# Eval_Board.net
KiCad netlist of a schematic drawn in Altium Designer
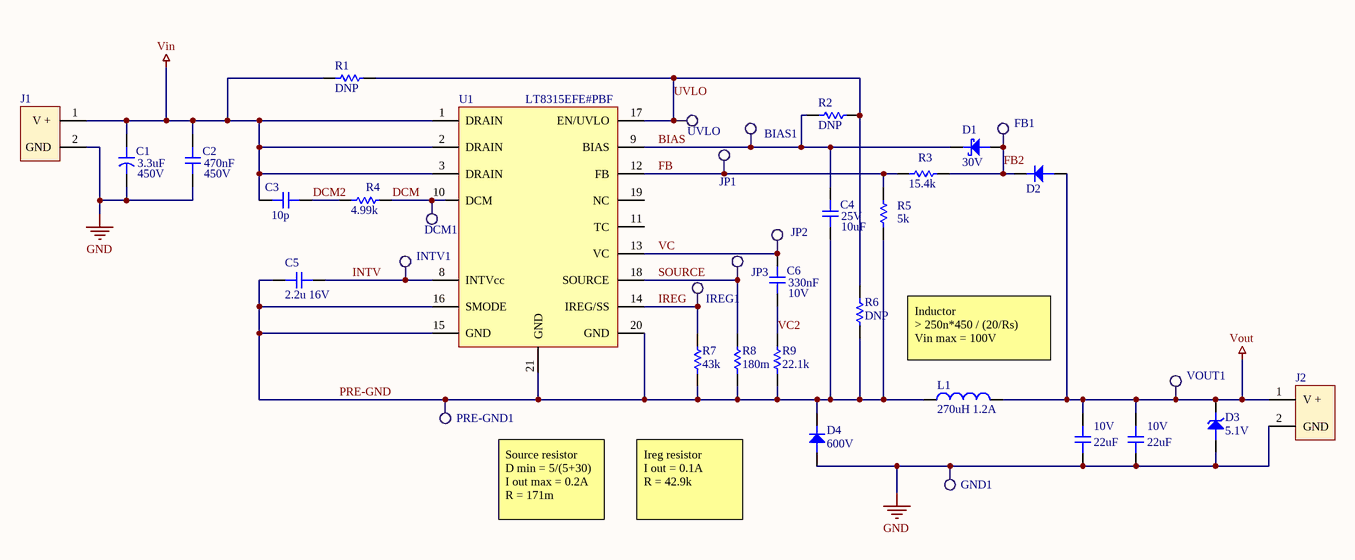
[diagram p0: Eval_Board.SchDoc]

(export (version "E")
  (design (tool "Eeschema 10.0.6"))
  (components
    (comp (ref "BIAS1")
      (value "Testpoint2")
      (footprint "TP2")
      (description "Single layer pad TP")
      (libsource (lib "Misc") (part "Testpoint2"))
    )
    (comp (ref "C1")
      (value "3.3uF 450V")
      (footprint "CAPAE125136X145M")
      (description "Al Cap UJ series SMT 3.3uF 450V")
      (fields
        (field (name "MANUFACTURER") "Nichicon")
        (field (name "MANUFACTURER PART NUMBER") "UUJ2W3R3MNQ1MS")
        (field (name "CAPACITANCE") "3.3uF")
        (field (name "VOLTAGE RATING (DC)") "450V")
      )
      (libsource (lib "DC_converter_sch") (part "UUJ2W3R3MNQ1MS"))
    )
    (comp (ref "C2")
      (value "0.47uF 450V 1812")
      (footprint "CAPC4532X28N")
      (description "Automotive Grade MLCC, 1812, X7T, 450V, 0.47 F, 20%, 2.30mm")
      (fields
        (field (name "MANUFACTURER") "TDK")
        (field (name "MANUFACTURER PART NUMBER") "CGA8N4X7T2W474M230KA")
        (field (name "CAPACITANCE") "470nF")
        (field (name "VOLTAGE RATING") "450V")
      )
      (libsource (lib "DC_converter_sch") (part "CGA8N4X7T2W474M230KA"))
    )
    (comp (ref "C3")
      (value "10p")
      (footprint "CAP-0805")
      (description "CAP CER 0805 10PF 25V")
      (fields
        (field (name "MANUFACTURER") "Murata")
        (field (name "MANUFACTURER PART NUMBER") "GCQ1555C1H9R6DB01D")
      )
      (libsource (lib "DC_converter_sch") (part "GCQ1555C1H9R6DB01D"))
    )
    (comp (ref "C4")
      (value "GRM21BR61E106MA73L")
      (footprint "CAP-0805")
      (description "Capacitor, 10 µF, 25 V, 0805 [2012 Metric], ± 20%, X5R, GRM Series")
      (fields
        (field (name "MANUFACTURER") "Murata")
        (field (name "TOLERANCE") "20%")
        (field (name "VOLTAGE RATING") "25V")
        (field (name "CAPACITANCE") "10uF")
      )
      (libsource (lib "DC_converter_sch") (part "GRM21BR61E106MA73L"))
    )
    (comp (ref "C5")
      (value "2.2u 16V")
      (footprint "CAP-0805")
      (description "Cap Ceramic 2.2uF 16V X7R 10% SMD 0805 125C Embossed T/R")
      (fields
        (field (name "MANUFACTURER") "Samsung")
        (field (name "MANUFACTURER PART NUMBER") "CL21B225KOFNFNE")
      )
      (libsource (lib "DC_converter_sch") (part "CL21B225KOFNFNE"))
    )
    (comp (ref "C6")
      (value "0.33u 10V")
      (footprint "CAP-0805")
      (description "CAP CER 0.33UF 10V X7R 0805")
      (fields
        (field (name "MANUFACTURER") "TDK")
        (field (name "MANUFACTURER PART NUMBER") "CGJ4J2X7R1A334K125AA")
        (field (name "VOLTAGE RATING") "10V")
        (field (name "CAPACITANCE") "330nF")
      )
      (libsource (lib "DC_converter_sch") (part "CGJ4J2X7R1A334K125AA"))
    )
    (comp (ref "C7")
      (value "GRM21BR61A226ME51L")
      (footprint "CAP-0805")
      (description "CAP, MLCC, X5R, 22UF, 10V, 0805")
      (fields
        (field (name "MANUFACTURER") "Murata")
        (field (name "TOLERANCE") "20%")
        (field (name "VOLTAGE RATING") "10V")
        (field (name "CAPACITANCE") "22uF")
      )
      (libsource (lib "DC_converter_sch") (part "GRM21BR61A226ME51L"))
    )
    (comp (ref "C8")
      (value "GRM21BR61A226ME51L")
      (footprint "CAP-0805")
      (description "CAP, MLCC, X5R, 22UF, 10V, 0805")
      (fields
        (field (name "MANUFACTURER") "Murata")
        (field (name "TOLERANCE") "20%")
        (field (name "VOLTAGE RATING") "10V")
        (field (name "CAPACITANCE") "22uF")
      )
      (libsource (lib "DC_converter_sch") (part "GRM21BR61A226ME51L"))
    )
    (comp (ref "D1")
      (value "30V")
      (footprint "PMEG3010EGWX")
      (fields
        (field (name "MANUFACTURER") "Nexperia")
        (field (name "MANUFACTURER PART NUMBER") "PMEG3010EGWX")
      )
      (libsource (lib "DC_converter_sch") (part "PMEG3010EGWX"))
    )
    (comp (ref "D2")
      (value "CMMR1U-06TRPBFREE")
      (footprint "SODFL375X108-2N")
      (fields (field (name "MANUFACTURER") "Central Semiconductor"))
      (libsource (lib "DC_converter_sch") (part "CMMR1U-06TRPBFREE"))
    )
    (comp (ref "D3")
      (value "5.1V")
      (footprint "SOT95P230X110-3N")
      (description "Zener Diode Single 5.1V 5% 60Ohm 250mW Automotive 3-Pin SOT-23 T/R")
      (fields
        (field (name "MANUFACTURER") "Nexperia")
        (field (name "MANUFACTURER PART NUMBER") "BZX84-C5V1,215")
      )
      (libsource (lib "DC_converter_sch") (part "BZX84-C5V1,215"))
    )
    (comp (ref "D4")
      (value "600V")
      (footprint "D3")
      (fields
        (field (name "MANUFACTURER") "Taiwan Semiconductor")
        (field (name "MANUFACTURER PART NUMBER") "HS2JFSM3G")
      )
      (libsource (lib "DC_converter_sch") (part "HS2JFSM3G"))
    )
    (comp (ref "DCM1")
      (value "Testpoint2")
      (footprint "TP2")
      (description "Single layer pad TP")
      (libsource (lib "Misc") (part "Testpoint2"))
    )
    (comp (ref "FB1")
      (value "Testpoint2")
      (footprint "TP2")
      (description "Single layer pad TP")
      (libsource (lib "Misc") (part "Testpoint2"))
    )
    (comp (ref "GND1")
      (value "Testpoint2")
      (footprint "TP2")
      (description "Single layer pad TP")
      (libsource (lib "Misc") (part "Testpoint2"))
    )
    (comp (ref "INTV1")
      (value "Testpoint2")
      (footprint "TP2")
      (description "Single layer pad TP")
      (libsource (lib "Misc") (part "Testpoint2"))
    )
    (comp (ref "IREG1")
      (value "Testpoint2")
      (footprint "TP2")
      (description "Single layer pad TP")
      (libsource (lib "Misc") (part "Testpoint2"))
    )
    (comp (ref "J1")
      (value "WM4153-ND")
      (footprint "2PIN")
      (description "CONN HEADER R/A 2POS 2.54MM")
      (fields (field (name "MANUFACTURER") "Molex") (field (name "MANUFACTURER PART NUMBER") "0705530106"))
      (libsource (lib "DC_converter_sch") (part "2PIN"))
    )
    (comp (ref "J2")
      (value "WM4153-ND")
      (footprint "2PIN")
      (description "CONN HEADER R/A 2POS 2.54MM")
      (fields (field (name "MANUFACTURER") "Molex") (field (name "MANUFACTURER PART NUMBER") "0705530106"))
      (libsource (lib "") (part "2PIN_1"))
    )
    (comp (ref "JP1")
      (value "Testpoint2")
      (footprint "TP2")
      (description "Single layer pad TP")
      (libsource (lib "Misc") (part "Testpoint2"))
    )
    (comp (ref "JP2")
      (value "Testpoint2")
      (footprint "TP2")
      (description "Single layer pad TP")
      (libsource (lib "Misc") (part "Testpoint2"))
    )
    (comp (ref "JP3")
      (value "Testpoint2")
      (footprint "TP2")
      (description "Single layer pad TP")
      (libsource (lib "Misc") (part "Testpoint2"))
    )
    (comp (ref "L1")
      (value "270uH 1.2A")
      (footprint "PCBComponent_1")
      (description "FIXED IND 270UH 1.2A 410 MOHM")
      (fields
        (field (name "MANUFACTURER") "Bourns")
        (field (name "MANUFACTURER PART NUMBER") "SDR1307-271KL")
      )
      (libsource (lib "DC_converter_sch") (part "SDR1307-271KL"))
    )
    (comp (ref "PRE-GND1")
      (value "Testpoint2")
      (footprint "TP2")
      (description "Single layer pad TP")
      (libsource (lib "Misc") (part "Testpoint2"))
    )
    (comp (ref "R1")
      (value "DNP")
      (footprint "RES-0805")
      (description "Res Thick Film 0805 100 Ohm 1% 1/8W ±100ppm/°C Molded SMD Paper T/R")
      (fields
        (field (name "MANUFACTURER") "Vishay Dale")
        (field (name "MANUFACTURER PART NUMBER") "CRCW0805100RFKEA")
      )
      (libsource (lib "DC_converter_sch") (part "CRCW0805100RFKEA"))
    )
    (comp (ref "R2")
      (value "DNP")
      (footprint "RES-0805")
      (description "Fixed Resistor, Metal Glaze/thick Film, 0.125W, 0ohm, Surface Mount, 0805")
      (fields
        (field (name "MANUFACTURER") "Yageo")
        (field (name "MANUFACTURER PART NUMBER") "AC0805JR-070RL")
      )
      (libsource (lib "DC_converter_sch") (part "AC0805JR-070RL"))
    )
    (comp (ref "R3")
      (value "RMCF0805FT15K4")
      (footprint "RES-0805")
      (description "RES 15.4K OHM 1% 1/8W 0805")
      (fields
        (field (name "MANUFACTURER") "Stackpole Electronics")
        (field (name "TOLERANCE") "1%")
        (field (name "RESISTANCE") "15.4k")
      )
      (libsource (lib "DC_converter_sch") (part "RMCF0805FT15K4"))
    )
    (comp (ref "R4")
      (value "RNCP0805FTD4K99")
      (footprint "RES-0805")
      (description "Res Thin Film 0805 4.99K Ohm 1% 0.25W(1/4W) ±100ppm/°C Sulfur Resistant Pad SMD T/R")
      (fields
        (field (name "MANUFACTURER") "Stackpole Electronics")
        (field (name "TOLERANCE") "1%")
        (field (name "RESISTANCE") "4.99k")
      )
      (libsource (lib "DC_converter_sch") (part "RNCP0805FTD4K99"))
    )
    (comp (ref "R5")
      (value "CRCW08055K00JNTA")
      (footprint "RES-0805")
      (description "Res SMD 5K Ohm 5% 1/8W 0805")
      (fields
        (field (name "MANUFACTURER") "Vishay Dale")
        (field (name "TOLERANCE") "5%")
        (field (name "RESISTANCE") "5k")
      )
      (libsource (lib "DC_converter_sch") (part "CRCW08055K00JNTA"))
    )
    (comp (ref "R6")
      (value "DNP")
      (footprint "RES-0805")
      (description "Res Thick Film 0805 1.6K Ohm 5% 1/8W ±100ppm/°C Molded SMD SMD Paper T/R")
      (fields
        (field (name "MANUFACTURER") "Stackpole Electronics")
        (field (name "MANUFACTURER PART NUMBER") "RMCF0805JT1K60")
      )
      (libsource (lib "DC_converter_sch") (part "RMCF0805JT1K60"))
    )
    (comp (ref "R7")
      (value "43k")
      (footprint "RESC2012X05N")
      (description "Res Thick Film 0805 43K Ohm 5% 0.125W(1/8W) ±200ppm/C Molded SMD Automotive Paper T/R")
      (fields
        (field (name "MANUFACTURER") "Vishay Dale")
        (field (name "MANUFACTURER PART NUMBER") "CRCW080543K0JNEA")
      )
      (libsource (lib "DC_converter_sch") (part "CRCW080543K0JNEA"))
    )
    (comp (ref "R8")
      (value "180m")
      (footprint "RES-0805")
      (description "0.18 Ohm 0805 1% 0.25W Rohs Compliant: Yes")
      (fields (field (name "MANUFACTURER") "Ohmite") (field (name "MANUFACTURER PART NUMBER") "KDV08FR180ET"))
      (libsource (lib "DC_converter_sch") (part "KDV08FR180ET"))
    )
    (comp (ref "R9")
      (value "22.1k")
      (footprint "RESC2012X06N")
      (description "Res Thick Film 0805 22.1K Ohm 1% 1/8W 100ppm/C Molded SMD SMD Paper T/R")
      (fields
        (field (name "MANUFACTURER") "Stackpole Electronics")
        (field (name "MANUFACTURER PART NUMBER") "RMCF0805FG22K1")
      )
      (libsource (lib "DC_converter_sch") (part "RMCF0805FG22K1"))
    )
    (comp (ref "U1")
      (value "LT8315EFE#PBF")
      (footprint "TSOP65P650X120-20N")
      (description "IC REG CTRLR FLYBACK 20TSSOP")
      (fields (field (name "MANUFACTURER") "Analog Devices / Linear Technology"))
      (libsource (lib "DC_converter_sch") (part "LT8315EFE#PBF"))
    )
    (comp (ref "UVLO")
      (value "Testpoint2")
      (footprint "TP2")
      (description "Single layer pad TP")
      (libsource (lib "Misc") (part "Testpoint2"))
    )
    (comp (ref "VOUT1")
      (value "Testpoint2")
      (footprint "TP2")
      (description "Single layer pad TP")
      (libsource (lib "Misc") (part "Testpoint2"))
    )
  )
  (nets
    (net (code "1") (name "/BIAS") (class "Default")
      (node (ref "BIAS1") (pin "1") (pinfunction "1_1") (pintype "passive"))
      (node (ref "C4") (pin "2") (pinfunction "2_2") (pintype "passive"))
      (node (ref "D1") (pin "1") (pinfunction "1_1") (pintype "passive"))
      (node (ref "R2") (pin "1") (pinfunction "1_1") (pintype "passive"))
      (node (ref "U1") (pin "9") (pinfunction "BIAS_9") (pintype "passive"))
    )
    (net (code "2") (name "/DCM") (class "Default")
      (node (ref "DCM1") (pin "1") (pinfunction "1_1") (pintype "passive"))
      (node (ref "R4") (pin "2") (pinfunction "2_2") (pintype "passive"))
      (node (ref "U1") (pin "10") (pinfunction "DCM_10") (pintype "passive"))
    )
    (net (code "3") (name "/DCM2") (class "Default")
      (node (ref "C3") (pin "2") (pinfunction "2_2") (pintype "passive"))
      (node (ref "R4") (pin "1") (pinfunction "1_1") (pintype "passive"))
    )
    (net (code "4") (name "/FB") (class "Default")
      (node (ref "JP1") (pin "1") (pinfunction "1_1") (pintype "passive"))
      (node (ref "R3") (pin "1") (pinfunction "1_1") (pintype "passive"))
      (node (ref "R5") (pin "2") (pinfunction "2_2") (pintype "passive"))
      (node (ref "U1") (pin "12") (pinfunction "FB_12") (pintype "passive"))
    )
    (net (code "5") (name "/FB2") (class "Default")
      (node (ref "D1") (pin "2") (pinfunction "2_2") (pintype "passive"))
      (node (ref "D2") (pin "1") (pinfunction "1_1") (pintype "passive"))
      (node (ref "FB1") (pin "1") (pinfunction "1_1") (pintype "passive"))
      (node (ref "R3") (pin "2") (pinfunction "2_2") (pintype "passive"))
    )
    (net (code "6") (name "/INTV") (class "Default")
      (node (ref "C5") (pin "2") (pinfunction "2_2") (pintype "passive"))
      (node (ref "INTV1") (pin "1") (pinfunction "1_1") (pintype "passive"))
      (node (ref "U1") (pin "8") (pinfunction "INTVcc_8") (pintype "passive"))
    )
    (net (code "7") (name "/IREG") (class "Default")
      (node (ref "IREG1") (pin "1") (pinfunction "1_1") (pintype "passive"))
      (node (ref "R7") (pin "2") (pinfunction "2_2") (pintype "passive"))
      (node (ref "U1") (pin "14") (pinfunction "IREG/SS_14") (pintype "passive"))
    )
    (net (code "8") (name "/PRE-GND") (class "Default")
      (node (ref "C4") (pin "1") (pinfunction "1_1") (pintype "passive"))
      (node (ref "C5") (pin "1") (pinfunction "1_1") (pintype "passive"))
      (node (ref "D4") (pin "1") (pinfunction "1_1") (pintype "passive"))
      (node (ref "L1") (pin "1") (pinfunction "1_1") (pintype "passive"))
      (node (ref "PRE-GND1") (pin "1") (pinfunction "1_1") (pintype "passive"))
      (node (ref "R5") (pin "1") (pinfunction "1_1") (pintype "passive"))
      (node (ref "R6") (pin "2") (pinfunction "2_2") (pintype "passive"))
      (node (ref "R7") (pin "1") (pinfunction "1_1") (pintype "passive"))
      (node (ref "R8") (pin "1") (pinfunction "1_1") (pintype "passive"))
      (node (ref "R9") (pin "1") (pinfunction "1_1") (pintype "passive"))
      (node (ref "U1") (pin "15") (pinfunction "GND_15") (pintype "passive"))
      (node (ref "U1") (pin "16") (pinfunction "SMODE_16") (pintype "passive"))
      (node (ref "U1") (pin "20") (pinfunction "GND_20") (pintype "passive"))
      (node (ref "U1") (pin "21") (pinfunction "GND_21") (pintype "passive"))
    )
    (net (code "9") (name "/SOURCE") (class "Default")
      (node (ref "JP3") (pin "1") (pinfunction "1_1") (pintype "passive"))
      (node (ref "R8") (pin "2") (pinfunction "2_2") (pintype "passive"))
      (node (ref "U1") (pin "18") (pinfunction "SOURCE_18") (pintype "passive"))
    )
    (net (code "10") (name "/UVLO") (class "Default")
      (node (ref "R1") (pin "2") (pinfunction "2_2") (pintype "passive"))
      (node (ref "R2") (pin "2") (pinfunction "2_2") (pintype "passive"))
      (node (ref "R6") (pin "1") (pinfunction "1_1") (pintype "passive"))
      (node (ref "U1") (pin "17") (pinfunction "EN/UVLO_17") (pintype "passive"))
      (node (ref "UVLO") (pin "1") (pinfunction "1_1") (pintype "passive"))
    )
    (net (code "11") (name "/VC") (class "Default")
      (node (ref "C6") (pin "2") (pinfunction "2_2") (pintype "passive"))
      (node (ref "JP2") (pin "1") (pinfunction "1_1") (pintype "passive"))
      (node (ref "U1") (pin "13") (pinfunction "VC_13") (pintype "passive"))
    )
    (net (code "12") (name "/VC2") (class "Default")
      (node (ref "C6") (pin "1") (pinfunction "1_1") (pintype "passive"))
      (node (ref "R9") (pin "2") (pinfunction "2_2") (pintype "passive"))
    )
    (net (code "13") (name "GND") (class "Default")
      (node (ref "C1") (pin "2") (pinfunction "2_2") (pintype "passive"))
      (node (ref "C2") (pin "2") (pinfunction "2_2") (pintype "passive"))
      (node (ref "C7") (pin "1") (pinfunction "1_1") (pintype "passive"))
      (node (ref "C8") (pin "1") (pinfunction "1_1") (pintype "passive"))
      (node (ref "D3") (pin "2") (pinfunction "2_2") (pintype "passive"))
      (node (ref "D4") (pin "2") (pinfunction "2_2") (pintype "passive"))
      (node (ref "GND1") (pin "1") (pinfunction "1_1") (pintype "passive"))
      (node (ref "J1") (pin "2") (pinfunction "GND_2") (pintype "passive"))
      (node (ref "J2") (pin "2") (pinfunction "GND_2") (pintype "passive"))
    )
    (net (code "14") (name "Vin") (class "Default")
      (node (ref "C1") (pin "1") (pinfunction "1_1") (pintype "passive"))
      (node (ref "C2") (pin "1") (pinfunction "1_1") (pintype "passive"))
      (node (ref "C3") (pin "1") (pinfunction "1_1") (pintype "passive"))
      (node (ref "J1") (pin "1") (pinfunction "V_+_1") (pintype "passive"))
      (node (ref "R1") (pin "1") (pinfunction "1_1") (pintype "passive"))
      (node (ref "U1") (pin "1") (pinfunction "DRAIN_1") (pintype "passive"))
      (node (ref "U1") (pin "2") (pinfunction "DRAIN_2") (pintype "passive"))
      (node (ref "U1") (pin "3") (pinfunction "DRAIN_3") (pintype "passive"))
    )
    (net (code "15") (name "Vout") (class "Default")
      (node (ref "C7") (pin "2") (pinfunction "2_2") (pintype "passive"))
      (node (ref "C8") (pin "2") (pinfunction "2_2") (pintype "passive"))
      (node (ref "D2") (pin "2") (pinfunction "2_2") (pintype "passive"))
      (node (ref "D3") (pin "1") (pinfunction "1_1") (pintype "passive"))
      (node (ref "J2") (pin "1") (pinfunction "V_+_1") (pintype "passive"))
      (node (ref "L1") (pin "2") (pinfunction "2_2") (pintype "passive"))
      (node (ref "VOUT1") (pin "1") (pinfunction "1_1") (pintype "passive"))
    )
    (net (code "16") (name "unconnected-(U1-NC-Pad19)") (class "Default")
      (node (ref "U1") (pin "19") (pinfunction "NC_19") (pintype "passive"))
    )
    (net (code "17") (name "unconnected-(U1-TC-Pad11)") (class "Default")
      (node (ref "U1") (pin "11") (pinfunction "TC_11") (pintype "passive"))
    )
  )
)
